# STM_System_Board.net
KiCad netlist of a schematic drawn in Altium Designer
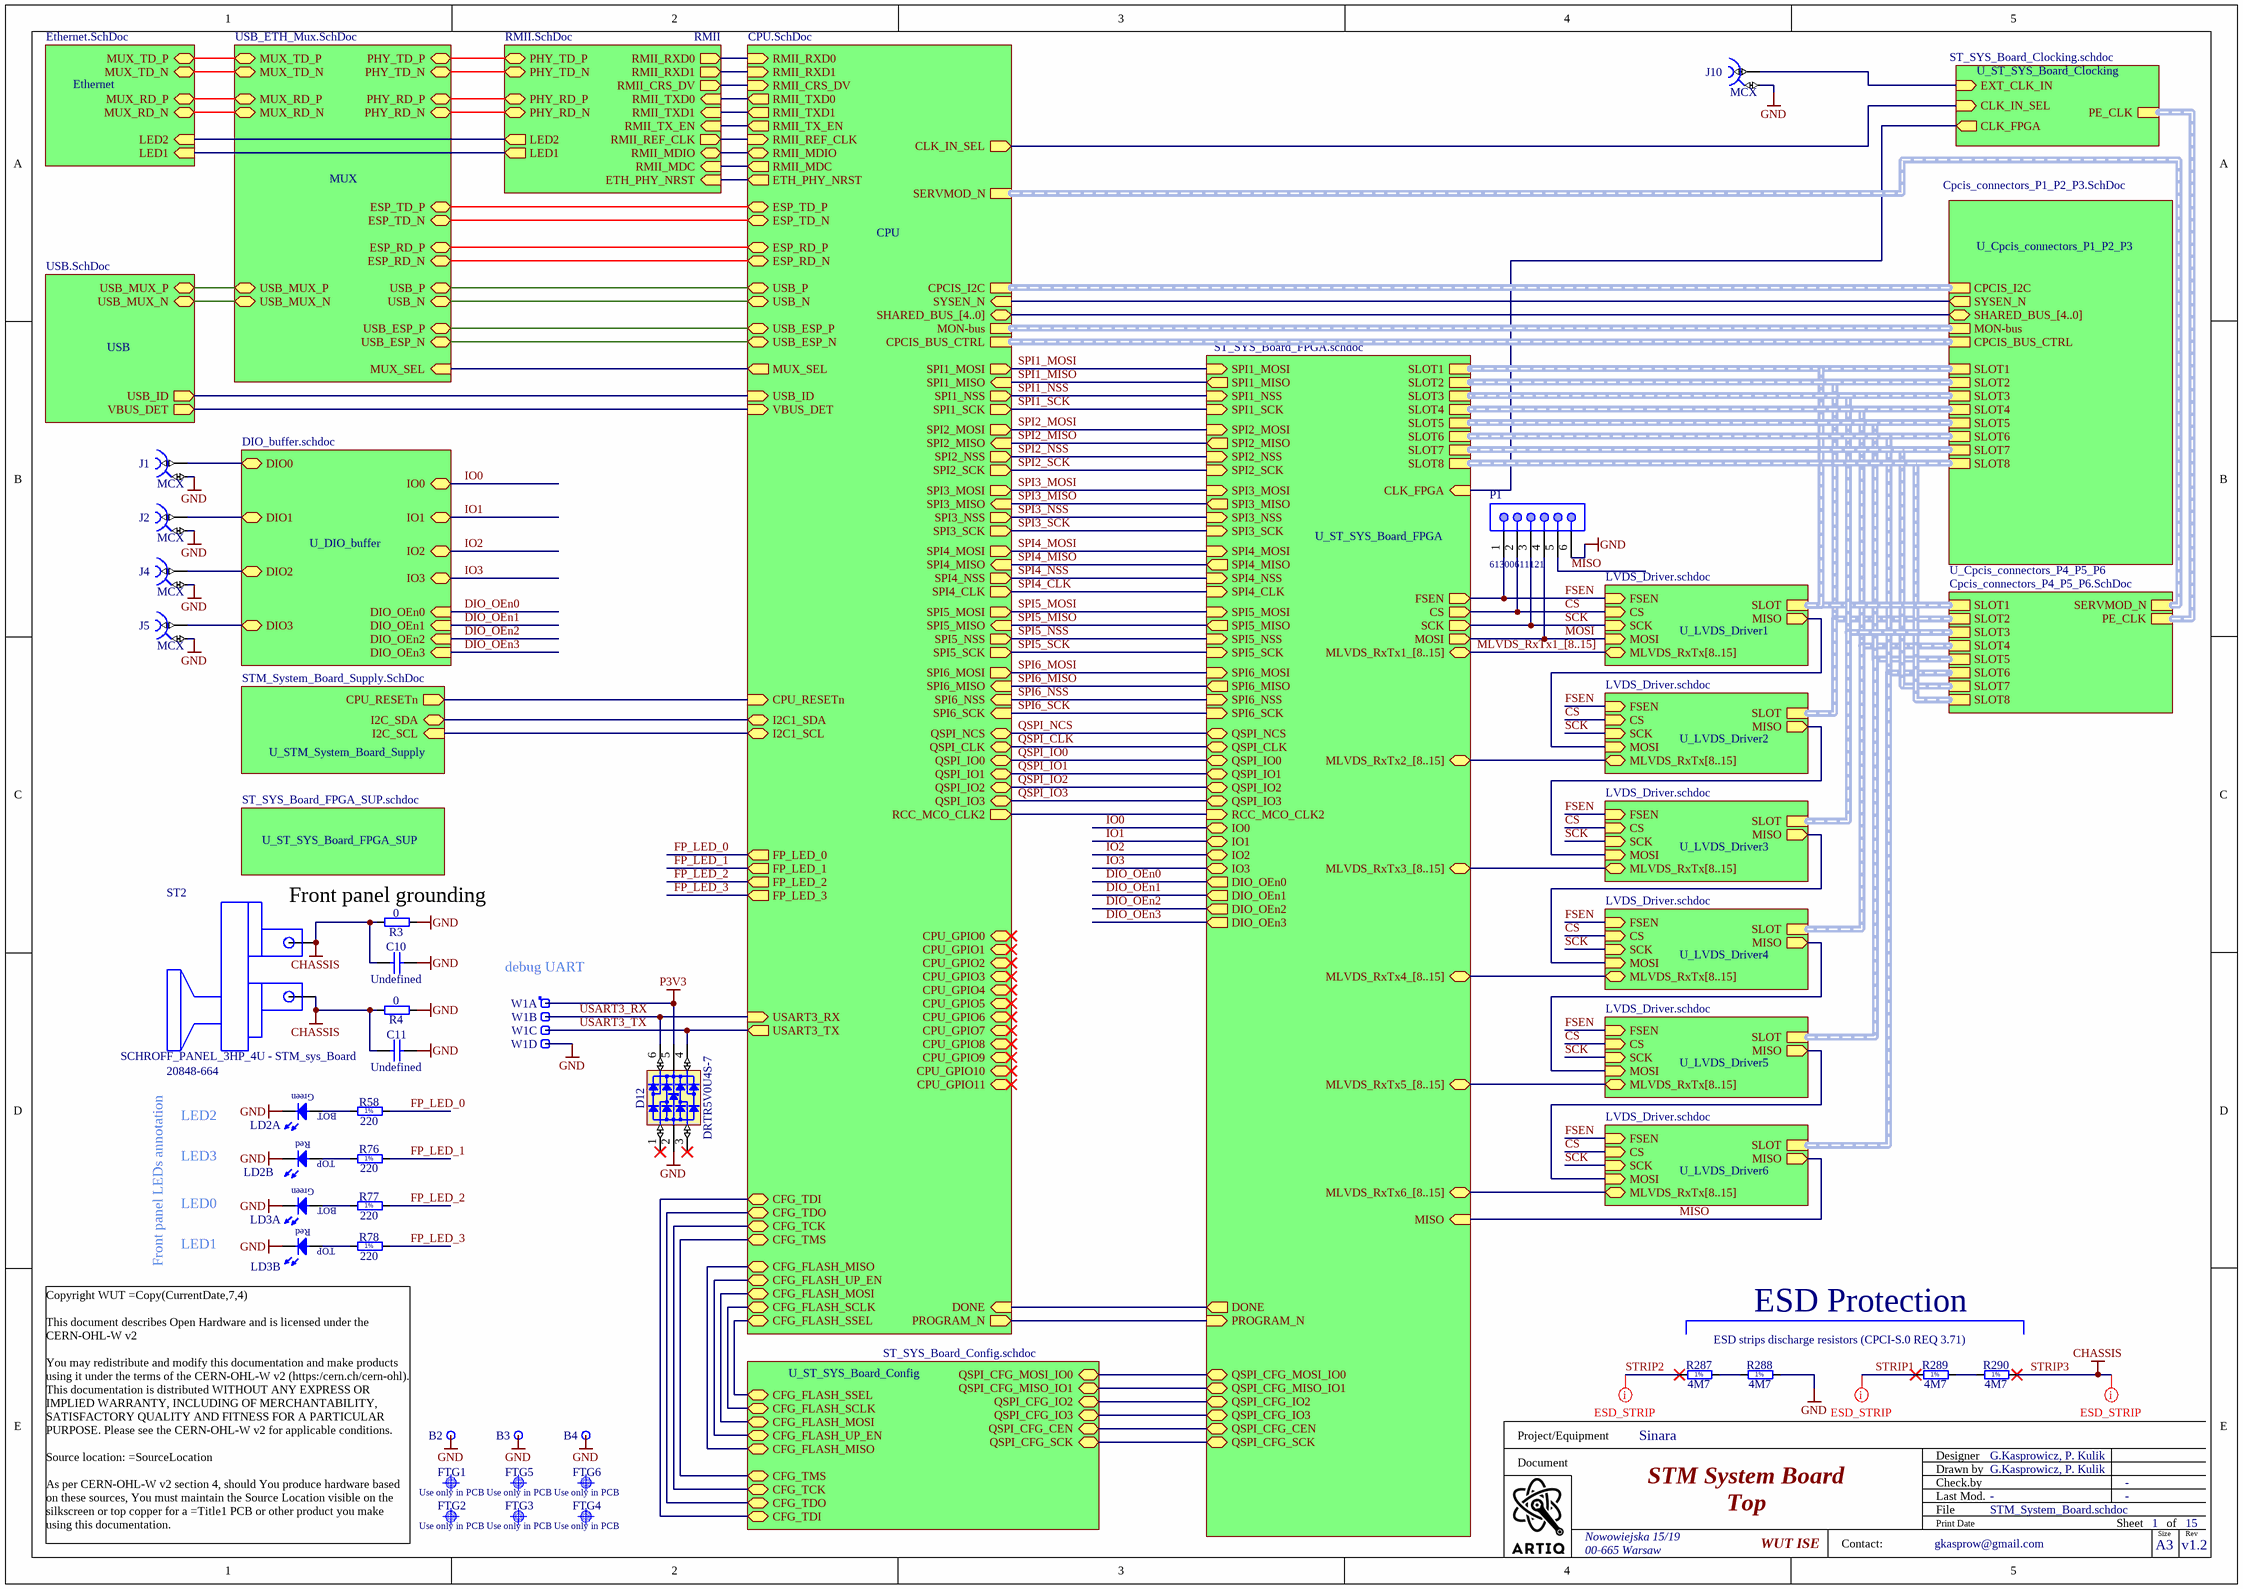
[diagram p0: STM_System_Board.schdoc]

(export (version "E")
  (design (tool "Eeschema 10.0.6"))
  (components
    (comp (ref "B2")
      (value "Plated Hole")
      (footprint "c170h100")
      (description "Single Terminal Socket")
      (fields (field (name "PART NUMBER") "PLATED_HOLE1.0_PAD1.7") (field (name "AUTHOR") "CERN DEM JLC"))
      (libsource (lib "Eletro-mechanical") (part "Single Terminal Socket"))
    )
    (comp (ref "B3")
      (value "Plated Hole")
      (footprint "c170h100")
      (description "Single Terminal Socket")
      (fields (field (name "PART NUMBER") "PLATED_HOLE1.0_PAD1.7") (field (name "AUTHOR") "CERN DEM JLC"))
      (libsource (lib "Eletro-mechanical") (part "Single Terminal Socket"))
    )
    (comp (ref "B4")
      (value "Plated Hole")
      (footprint "c170h100")
      (description "Single Terminal Socket")
      (fields (field (name "PART NUMBER") "PLATED_HOLE1.0_PAD1.7") (field (name "AUTHOR") "CERN DEM JLC"))
      (libsource (lib "Eletro-mechanical") (part "Single Terminal Socket"))
    )
    (comp (ref "C10")
      (value "Undefined")
      (footprint "CAPC2012X135N")
      (description "Non-polarised capacitor")
      (fields (field (name "PART NUMBER") "CC0805_NO-VALUE") (field (name "AUTHOR") "CERN DEM JLC"))
      (libsource (lib "Capacitors") (part "Capacitor - non polarized"))
    )
    (comp (ref "C11")
      (value "Undefined")
      (footprint "CAPC2012X135N")
      (description "Non-polarised capacitor")
      (fields (field (name "PART NUMBER") "CC0805_NO-VALUE") (field (name "AUTHOR") "CERN DEM JLC"))
      (libsource (lib "Capacitors") (part "Capacitor - non polarized"))
    )
    (comp (ref "D12")
      (value "DRTR5V0U4S-7")
      (footprint "SOT65P210X110-6N")
      (description "Integrated Quad Ultra-Low Capacitance ESD Protection")
      (fields (field (name "MANUFACTURER") "DIODES") (field (name "AUTHOR") "GK"))
      (libsource (lib "Diodes") (part "D_TVS_DRTR5V0U4S-7"))
    )
    (comp (ref "FTG1")
      (value "Use only in PCB")
      (footprint "FIDUCIAL_TOP_C100-200")
      (description "Fiducial Target")
      (fields (field (name "PART NUMBER") "FIDUCIAL_TARGET_C100-200") (field (name "AUTHOR") "CERN DEM JLC"))
      (libsource (lib "Eletro-mechanical") (part "Fiducial Target"))
    )
    (comp (ref "FTG2")
      (value "Use only in PCB")
      (footprint "FIDUCIAL_TOP_S100-200")
      (description "Fiducial Target")
      (fields (field (name "PART NUMBER") "FIDUCIAL_TARGET_S100-200") (field (name "AUTHOR") "CERN DEM JLC"))
      (libsource (lib "Eletro-mechanical") (part "Fiducial Target"))
    )
    (comp (ref "FTG3")
      (value "Use only in PCB")
      (footprint "FIDUCIAL_TOP_S100-200")
      (description "Fiducial Target")
      (fields (field (name "PART NUMBER") "FIDUCIAL_TARGET_S100-200") (field (name "AUTHOR") "CERN DEM JLC"))
      (libsource (lib "Eletro-mechanical") (part "Fiducial Target"))
    )
    (comp (ref "FTG4")
      (value "Use only in PCB")
      (footprint "FIDUCIAL_TOP_S100-200")
      (description "Fiducial Target")
      (fields (field (name "PART NUMBER") "FIDUCIAL_TARGET_S100-200") (field (name "AUTHOR") "CERN DEM JLC"))
      (libsource (lib "Eletro-mechanical") (part "Fiducial Target"))
    )
    (comp (ref "FTG5")
      (value "Use only in PCB")
      (footprint "FIDUCIAL_TOP_C100-200")
      (description "Fiducial Target")
      (fields (field (name "PART NUMBER") "FIDUCIAL_TARGET_C100-200") (field (name "AUTHOR") "CERN DEM JLC"))
      (libsource (lib "Eletro-mechanical") (part "Fiducial Target"))
    )
    (comp (ref "FTG6")
      (value "Use only in PCB")
      (footprint "FIDUCIAL_TOP_C100-200")
      (description "Fiducial Target")
      (fields (field (name "PART NUMBER") "FIDUCIAL_TARGET_C100-200") (field (name "AUTHOR") "CERN DEM JLC"))
      (libsource (lib "Eletro-mechanical") (part "Fiducial Target"))
    )
    (comp (ref "J1")
      (value "MCX")
      (footprint "AMPHENOL_919-383J-51A")
      (fields
        (field (name "PART NUMBER") "AMPHENOL_919-383J-51A")
        (field (name "MANUFACTURER") "AMPHENOL")
        (field (name "MANUFACTURER PART NUMBER") "919-383J-51A")
        (field (name "AUTHOR") "CERN DEM BC")
      )
      (libsource (lib "Connectors") (part "Coax_1Female_1Shield"))
    )
    (comp (ref "J2")
      (value "MCX")
      (footprint "AMPHENOL_919-383J-51A")
      (fields
        (field (name "PART NUMBER") "AMPHENOL_919-383J-51A")
        (field (name "MANUFACTURER") "AMPHENOL")
        (field (name "MANUFACTURER PART NUMBER") "919-383J-51A")
        (field (name "AUTHOR") "CERN DEM BC")
      )
      (libsource (lib "Connectors") (part "Coax_1Female_1Shield"))
    )
    (comp (ref "J4")
      (value "MCX")
      (footprint "AMPHENOL_919-383J-51A")
      (fields
        (field (name "PART NUMBER") "AMPHENOL_919-383J-51A")
        (field (name "MANUFACTURER") "AMPHENOL")
        (field (name "MANUFACTURER PART NUMBER") "919-383J-51A")
        (field (name "AUTHOR") "CERN DEM BC")
      )
      (libsource (lib "Connectors") (part "Coax_1Female_1Shield"))
    )
    (comp (ref "J5")
      (value "MCX")
      (footprint "AMPHENOL_919-383J-51A")
      (fields
        (field (name "PART NUMBER") "AMPHENOL_919-383J-51A")
        (field (name "MANUFACTURER") "AMPHENOL")
        (field (name "MANUFACTURER PART NUMBER") "919-383J-51A")
        (field (name "AUTHOR") "CERN DEM BC")
      )
      (libsource (lib "Connectors") (part "Coax_1Female_1Shield"))
    )
    (comp (ref "J10")
      (value "MCX")
      (footprint "AMPHENOL_919-383J-51A")
      (fields
        (field (name "PART NUMBER") "AMPHENOL_919-383J-51A")
        (field (name "MANUFACTURER") "AMPHENOL")
        (field (name "MANUFACTURER PART NUMBER") "919-383J-51A")
        (field (name "AUTHOR") "CERN DEM BC")
      )
      (libsource (lib "Connectors") (part "Coax_1Female_1Shield"))
    )
    (comp (ref "LD2")
      (value "Red/Green")
      (footprint "LED_DIALIGHT_571-0112F")
      (description "2x LED  Botom Green, Top Red")
      (fields
        (field (name "PART NUMBER") "LED_DIALIGHT_571-0112F")
        (field (name "MANUFACTURER") "DIALIGHT")
        (field (name "AUTHOR") "CERN DEM JLC")
      )
      (libsource (lib "ICs And Semiconductors") (part "LED x2 G-1C2A-BOT_R-3C4A-TOP"))
    )
    (comp (ref "LD3")
      (value "Red/Green")
      (footprint "LED_DIALIGHT_571-0112F")
      (description "2x LED  Botom Green, Top Red")
      (fields
        (field (name "PART NUMBER") "LED_DIALIGHT_571-0112F")
        (field (name "MANUFACTURER") "DIALIGHT")
        (field (name "AUTHOR") "CERN DEM JLC")
      )
      (libsource (lib "ICs And Semiconductors") (part "LED x2 G-1C2A-BOT_R-3C4A-TOP"))
    )
    (comp (ref "P1")
      (value "61300611121")
      (footprint "61300611121")
      (description "WR-PHD Pin Header, THT, pitch 2.54mm, Single Row, Vertical, 6p")
      (fields (field (name "MANUFACTURER") "Wurth Elektronik"))
      (libsource (lib "Altium_WR-PHD (rev20a)") (part "61300611121"))
    )
    (comp (ref "R3")
      (value "0")
      (footprint "RESC1608X55N")
      (description "Resistor")
      (fields
        (field (name "PART NUMBER") "R0603_0R_JUMPER")
        (field (name "MANUFACTURER") "GENERIC")
        (field (name "AUTHOR") "CERN DEM JLC")
      )
      (libsource (lib "Resistors") (part "Resistor"))
    )
    (comp (ref "R4")
      (value "0")
      (footprint "RESC1608X55N")
      (description "Resistor")
      (fields
        (field (name "PART NUMBER") "R0603_0R_JUMPER")
        (field (name "MANUFACTURER") "GENERIC")
        (field (name "AUTHOR") "CERN DEM JLC")
      )
      (libsource (lib "Resistors") (part "Resistor"))
    )
    (comp (ref "R58")
      (value "220")
      (footprint "RESC1608X55N")
      (description "Resistor - 1%")
      (fields
        (field (name "PART NUMBER") "R0603_220R_1%_0.1W_100PPM")
        (field (name "POWER") "0.1W")
        (field (name "AUTHOR") "CERN DEM JLC")
      )
      (libsource (lib "Resistors") (part "Resistor - 1%"))
    )
    (comp (ref "R76")
      (value "220")
      (footprint "RESC1608X55N")
      (description "Resistor - 1%")
      (fields
        (field (name "PART NUMBER") "R0603_220R_1%_0.1W_100PPM")
        (field (name "POWER") "0.1W")
        (field (name "AUTHOR") "CERN DEM JLC")
      )
      (libsource (lib "Resistors") (part "Resistor - 1%"))
    )
    (comp (ref "R77")
      (value "220")
      (footprint "RESC1608X55N")
      (description "Resistor - 1%")
      (fields
        (field (name "PART NUMBER") "R0603_220R_1%_0.1W_100PPM")
        (field (name "POWER") "0.1W")
        (field (name "AUTHOR") "CERN DEM JLC")
      )
      (libsource (lib "Resistors") (part "Resistor - 1%"))
    )
    (comp (ref "R78")
      (value "220")
      (footprint "RESC1608X55N")
      (description "Resistor - 1%")
      (fields
        (field (name "PART NUMBER") "R0603_220R_1%_0.1W_100PPM")
        (field (name "POWER") "0.1W")
        (field (name "AUTHOR") "CERN DEM JLC")
      )
      (libsource (lib "Resistors") (part "Resistor - 1%"))
    )
    (comp (ref "R287")
      (value "4M7")
      (footprint "RESC2113X55N")
      (description "Resistor - 1%")
      (fields
        (field (name "PART NUMBER") "R0805_4M7_1%_0.125W_100PPM_VISHAY_CRCW e3")
        (field (name "POWER") "0.125W")
        (field (name "AUTHOR") "CERN DEM BR")
      )
      (libsource (lib "Resistors") (part "Resistor - 1%"))
    )
    (comp (ref "R288")
      (value "4M7")
      (footprint "RESC2113X55N")
      (description "Resistor - 1%")
      (fields
        (field (name "PART NUMBER") "R0805_4M7_1%_0.125W_100PPM_VISHAY_CRCW e3")
        (field (name "POWER") "0.125W")
        (field (name "AUTHOR") "CERN DEM BR")
      )
      (libsource (lib "Resistors") (part "Resistor - 1%"))
    )
    (comp (ref "R289")
      (value "4M7")
      (footprint "RESC2113X55N")
      (description "Resistor - 1%")
      (fields
        (field (name "PART NUMBER") "R0805_4M7_1%_0.125W_100PPM_VISHAY_CRCW e3")
        (field (name "POWER") "0.125W")
        (field (name "AUTHOR") "CERN DEM BR")
      )
      (libsource (lib "Resistors") (part "Resistor - 1%"))
    )
    (comp (ref "R290")
      (value "4M7")
      (footprint "RESC2113X55N")
      (description "Resistor - 1%")
      (fields
        (field (name "PART NUMBER") "R0805_4M7_1%_0.125W_100PPM_VISHAY_CRCW e3")
        (field (name "POWER") "0.125W")
        (field (name "AUTHOR") "CERN DEM BR")
      )
      (libsource (lib "Resistors") (part "Resistor - 1%"))
    )
    (comp (ref "ST2")
      (value "SCHROFF_PANEL_3HP_4U - STM_sys_Board")
      (footprint "SCHROFF_PANEL_3HP_4U - STM_sys_Board")
      (description "Schroff 3HP 4U EUROCARD Panel")
      (fields
        (field (name "MANUFACTURER") "Schroff")
        (field (name "MANUFACTURER PART NUMBER") "20818-017")
        (field (name "MANUFACTURER PART NUMBER 2") "20848-664")
      )
      (libsource (lib "Mechanical") (part "SCHROFF_PANEL_3HP_4U - STM_sys_Board"))
    )
    (comp (ref "W1")
      (value "Header 4")
      (footprint "SAMTEC_HTSW-104-23-L-S")
      (description "4 Mini Wire-Wrap Contact Strip Header")
      (fields
        (field (name "PART NUMBER") "SAMTEC_HTSW-104-23-L-S")
        (field (name "MANUFACTURER") "SAMTEC")
        (field (name "AUTHOR") "CERN DEM JLC")
      )
      (libsource (lib "Connectors") (part "Wire-Wrap Contact x4"))
    )
  )
  (nets
    (net (code "35") (name "/CS") (class "Default")
      (node (ref "P1") (pin "2") (pinfunction "2_2") (pintype "passive"))
    )
    (net (code "36") (name "/DIO0") (class "Default")
      (node (ref "J1") (pin "1") (pinfunction "1_1") (pintype "bidirectional"))
    )
    (net (code "37") (name "/DIO1") (class "Default")
      (node (ref "J2") (pin "1") (pinfunction "1_1") (pintype "bidirectional"))
    )
    (net (code "38") (name "/DIO2") (class "Default")
      (node (ref "J4") (pin "1") (pinfunction "1_1") (pintype "bidirectional"))
    )
    (net (code "39") (name "/DIO3") (class "Default")
      (node (ref "J5") (pin "1") (pinfunction "1_1") (pintype "bidirectional"))
    )
    (net (code "50") (name "/EXT_CLK_IN") (class "Default")
      (node (ref "J10") (pin "1") (pinfunction "1_1") (pintype "bidirectional"))
    )
    (net (code "51") (name "/FP_LED_0") (class "Default")
      (node (ref "R58") (pin "2") (pinfunction "2_2") (pintype "passive"))
    )
    (net (code "52") (name "/FP_LED_1") (class "Default")
      (node (ref "R76") (pin "2") (pinfunction "2_2") (pintype "passive"))
    )
    (net (code "53") (name "/FP_LED_2") (class "Default")
      (node (ref "R77") (pin "2") (pinfunction "2_2") (pintype "passive"))
    )
    (net (code "54") (name "/FP_LED_3") (class "Default")
      (node (ref "R78") (pin "2") (pinfunction "2_2") (pintype "passive"))
    )
    (net (code "55") (name "/FSEN") (class "Default")
      (node (ref "P1") (pin "1") (pinfunction "1_1") (pintype "passive"))
    )
    (net (code "64") (name "/MISO") (class "Default")
      (node (ref "P1") (pin "5") (pinfunction "5_5") (pintype "passive"))
    )
    (net (code "77") (name "/MOSI") (class "Default")
      (node (ref "P1") (pin "4") (pinfunction "4_4") (pintype "passive"))
    )
    (net (code "111") (name "/SCK") (class "Default")
      (node (ref "P1") (pin "3") (pinfunction "3_3") (pintype "passive"))
    )
    (net (code "146") (name "/STRIP1") (class "Default")
      (node (ref "R289") (pin "1") (pinfunction "1_1") (pintype "passive+no_connect"))
    )
    (net (code "147") (name "/STRIP2") (class "Default")
      (node (ref "R287") (pin "1") (pinfunction "1_1") (pintype "passive+no_connect"))
    )
    (net (code "149") (name "/USART3_RX") (class "Default")
      (node (ref "D12") (pin "6") (pinfunction "I/O4_6") (pintype "bidirectional"))
      (node (ref "W1") (pin "2") (pinfunction "2_2") (pintype "bidirectional"))
    )
    (net (code "150") (name "/USART3_TX") (class "Default")
      (node (ref "D12") (pin "4") (pinfunction "I/O3_4") (pintype "bidirectional"))
      (node (ref "W1") (pin "3") (pinfunction "3_3") (pintype "bidirectional"))
    )
    (net (code "159") (name "CHASSIS") (class "Default")
      (node (ref "C10") (pin "1") (pinfunction "1_1") (pintype "passive"))
      (node (ref "C11") (pin "1") (pinfunction "1_1") (pintype "passive"))
      (node (ref "R290") (pin "2") (pinfunction "2_2") (pintype "passive"))
      (node (ref "R3") (pin "2") (pinfunction "2_2") (pintype "passive"))
      (node (ref "R4") (pin "2") (pinfunction "2_2") (pintype "passive"))
      (node (ref "ST2") (pin "0") (pinfunction "0_0") (pintype "passive"))
      (node (ref "ST2") (pin "1") (pinfunction "1_1") (pintype "passive"))
    )
    (net (code "160") (name "GND") (class "Default")
      (node (ref "B2") (pin "1") (pinfunction "1_1") (pintype "bidirectional"))
      (node (ref "B3") (pin "1") (pinfunction "1_1") (pintype "bidirectional"))
      (node (ref "B4") (pin "1") (pinfunction "1_1") (pintype "bidirectional"))
      (node (ref "C10") (pin "2") (pinfunction "2_2") (pintype "passive"))
      (node (ref "C11") (pin "2") (pinfunction "2_2") (pintype "passive"))
      (node (ref "D12") (pin "2") (pinfunction "GND_2") (pintype "power_in"))
      (node (ref "J1") (pin "2") (pinfunction "2_2") (pintype "bidirectional"))
      (node (ref "J10") (pin "2") (pinfunction "2_2") (pintype "bidirectional"))
      (node (ref "J2") (pin "2") (pinfunction "2_2") (pintype "bidirectional"))
      (node (ref "J4") (pin "2") (pinfunction "2_2") (pintype "bidirectional"))
      (node (ref "J5") (pin "2") (pinfunction "2_2") (pintype "bidirectional"))
      (node (ref "LD2") (pin "1") (pinfunction "C_1") (pintype "passive"))
      (node (ref "LD2") (pin "3") (pinfunction "C_3") (pintype "passive"))
      (node (ref "LD3") (pin "1") (pinfunction "C_1") (pintype "passive"))
      (node (ref "LD3") (pin "3") (pinfunction "C_3") (pintype "passive"))
      (node (ref "P1") (pin "6") (pinfunction "6_6") (pintype "passive"))
      (node (ref "R288") (pin "2") (pinfunction "2_2") (pintype "passive"))
      (node (ref "R3") (pin "1") (pinfunction "1_1") (pintype "passive"))
      (node (ref "R4") (pin "1") (pinfunction "1_1") (pintype "passive"))
      (node (ref "W1") (pin "4") (pinfunction "4_4") (pintype "bidirectional"))
    )
    (net (code "161") (name "Net-(LD2A-A)") (class "Default")
      (node (ref "LD2") (pin "2") (pinfunction "A_2") (pintype "passive"))
      (node (ref "R58") (pin "1") (pinfunction "1_1") (pintype "passive"))
    )
    (net (code "162") (name "Net-(LD2B-A)") (class "Default")
      (node (ref "LD2") (pin "4") (pinfunction "A_4") (pintype "passive"))
      (node (ref "R76") (pin "1") (pinfunction "1_1") (pintype "passive"))
    )
    (net (code "163") (name "Net-(LD3A-A)") (class "Default")
      (node (ref "LD3") (pin "2") (pinfunction "A_2") (pintype "passive"))
      (node (ref "R77") (pin "1") (pinfunction "1_1") (pintype "passive"))
    )
    (net (code "164") (name "Net-(LD3B-A)") (class "Default")
      (node (ref "LD3") (pin "4") (pinfunction "A_4") (pintype "passive"))
      (node (ref "R78") (pin "1") (pinfunction "1_1") (pintype "passive"))
    )
    (net (code "165") (name "Net-(R287-Pad2)") (class "Default")
      (node (ref "R287") (pin "2") (pinfunction "2_2") (pintype "passive"))
      (node (ref "R288") (pin "1") (pinfunction "1_1") (pintype "passive"))
    )
    (net (code "166") (name "Net-(R289-Pad2)") (class "Default")
      (node (ref "R289") (pin "2") (pinfunction "2_2") (pintype "passive"))
      (node (ref "R290") (pin "1") (pinfunction "1_1") (pintype "passive"))
    )
    (net (code "167") (name "P3V3") (class "Default")
      (node (ref "D12") (pin "5") (pinfunction "VBUS_5") (pintype "power_in"))
      (node (ref "W1") (pin "1") (pinfunction "1_1") (pintype "bidirectional"))
    )
    (net (code "168") (name "unconnected-(D12-I{slash}O1-Pad1)") (class "Default")
      (node (ref "D12") (pin "1") (pinfunction "I/O1_1") (pintype "bidirectional+no_connect"))
    )
    (net (code "169") (name "unconnected-(D12-I{slash}O2-Pad3)") (class "Default")
      (node (ref "D12") (pin "3") (pinfunction "I/O2_3") (pintype "bidirectional+no_connect"))
    )
  )
)
